# LedBtn.net
KiCad netlist of a schematic drawn in Altium Designer
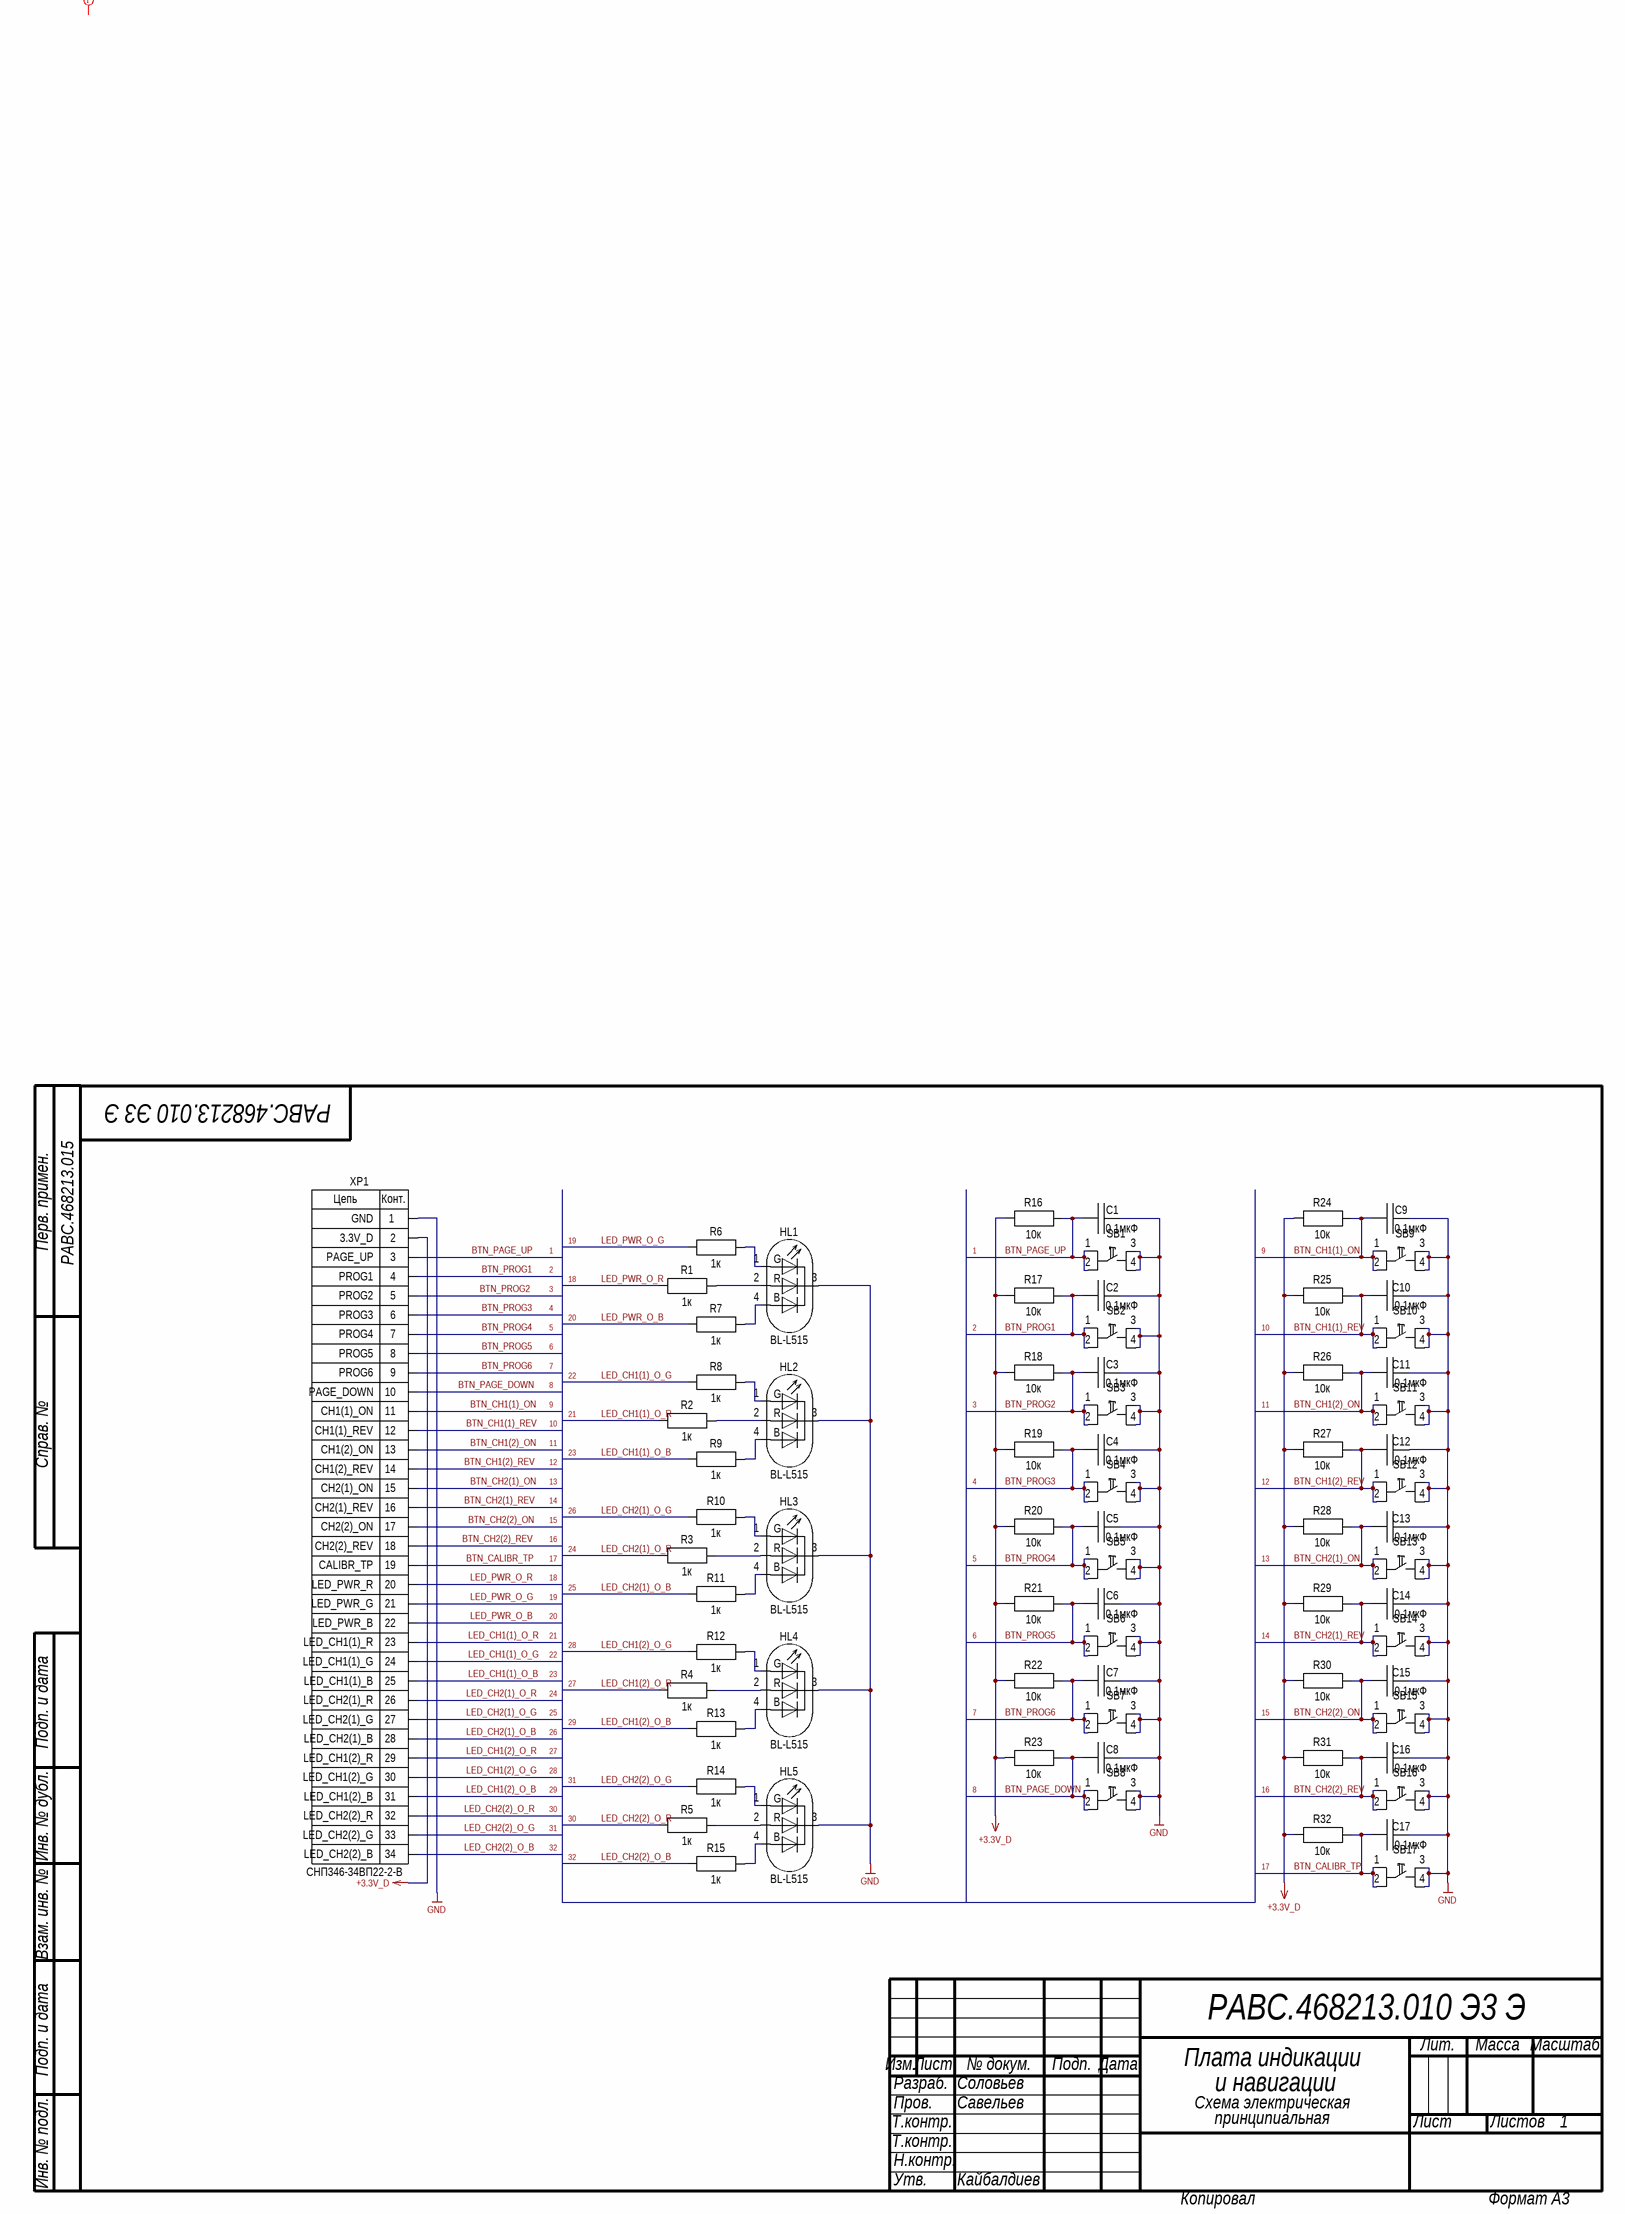
[diagram p0: LedBtn.SchDoc]

(export (version "E")
  (design (tool "Eeschema 10.0.6"))
  (components
    (comp (ref "C1")
      (value "0,1мкФ")
      (footprint "Cap0805")
      (fields
        (field (name "PARTNUMBER") "К10-84в-2012М-50 В-Н90-0,1 мкФ+80 %-20 %-N-A")
        (field (name "MANUFACTURER") "ОАО «ВЗРД Монолит»")
        (field (name "Comment") "Capacitor")
      )
      (libsource (lib "AltiumBase new") (part "Capacitor"))
    )
    (comp (ref "C2")
      (value "0,1мкФ")
      (footprint "Cap0805")
      (fields
        (field (name "PARTNUMBER") "К10-84в-2012М-50 В-Н90-0,1 мкФ+80 %-20 %-N-A")
        (field (name "MANUFACTURER") "ОАО «ВЗРД Монолит»")
        (field (name "Comment") "Capacitor")
      )
      (libsource (lib "AltiumBase new") (part "Capacitor"))
    )
    (comp (ref "C3")
      (value "0,1мкФ")
      (footprint "Cap0805")
      (fields
        (field (name "PARTNUMBER") "К10-84в-2012М-50 В-Н90-0,1 мкФ+80 %-20 %-N-A")
        (field (name "MANUFACTURER") "ОАО «ВЗРД Монолит»")
        (field (name "Comment") "Capacitor")
      )
      (libsource (lib "AltiumBase new") (part "Capacitor"))
    )
    (comp (ref "C4")
      (value "0,1мкФ")
      (footprint "Cap0805")
      (fields
        (field (name "PARTNUMBER") "К10-84в-2012М-50 В-Н90-0,1 мкФ+80 %-20 %-N-A")
        (field (name "MANUFACTURER") "ОАО «ВЗРД Монолит»")
        (field (name "Comment") "Capacitor")
      )
      (libsource (lib "AltiumBase new") (part "Capacitor"))
    )
    (comp (ref "C5")
      (value "0,1мкФ")
      (footprint "Cap0805")
      (fields
        (field (name "PARTNUMBER") "К10-84в-2012М-50 В-Н90-0,1 мкФ+80 %-20 %-N-A")
        (field (name "MANUFACTURER") "ОАО «ВЗРД Монолит»")
        (field (name "Comment") "Capacitor")
      )
      (libsource (lib "AltiumBase new") (part "Capacitor"))
    )
    (comp (ref "C6")
      (value "0,1мкФ")
      (footprint "Cap0805")
      (fields
        (field (name "PARTNUMBER") "К10-84в-2012М-50 В-Н90-0,1 мкФ+80 %-20 %-N-A")
        (field (name "MANUFACTURER") "ОАО «ВЗРД Монолит»")
        (field (name "Comment") "Capacitor")
      )
      (libsource (lib "AltiumBase new") (part "Capacitor"))
    )
    (comp (ref "C7")
      (value "0,1мкФ")
      (footprint "Cap0805")
      (fields
        (field (name "PARTNUMBER") "К10-84в-2012М-50 В-Н90-0,1 мкФ+80 %-20 %-N-A")
        (field (name "MANUFACTURER") "ОАО «ВЗРД Монолит»")
        (field (name "Comment") "Capacitor")
      )
      (libsource (lib "AltiumBase new") (part "Capacitor"))
    )
    (comp (ref "C8")
      (value "0,1мкФ")
      (footprint "Cap0805")
      (fields
        (field (name "PARTNUMBER") "К10-84в-2012М-50 В-Н90-0,1 мкФ+80 %-20 %-N-A")
        (field (name "MANUFACTURER") "ОАО «ВЗРД Монолит»")
        (field (name "Comment") "Capacitor")
      )
      (libsource (lib "AltiumBase new") (part "Capacitor"))
    )
    (comp (ref "C9")
      (value "0,1мкФ")
      (footprint "Cap0805")
      (fields
        (field (name "PARTNUMBER") "К10-84в-2012М-50 В-Н90-0,1 мкФ+80 %-20 %-N-A")
        (field (name "MANUFACTURER") "ОАО «ВЗРД Монолит»")
        (field (name "Comment") "Capacitor")
      )
      (libsource (lib "AltiumBase new") (part "Capacitor"))
    )
    (comp (ref "C10")
      (value "0,1мкФ")
      (footprint "Cap0805")
      (fields
        (field (name "PARTNUMBER") "К10-84в-2012М-50 В-Н90-0,1 мкФ+80 %-20 %-N-A")
        (field (name "MANUFACTURER") "ОАО «ВЗРД Монолит»")
        (field (name "Comment") "Capacitor")
      )
      (libsource (lib "AltiumBase new") (part "Capacitor"))
    )
    (comp (ref "C11")
      (value "0,1мкФ")
      (footprint "Cap0805")
      (fields
        (field (name "PARTNUMBER") "К10-84в-2012М-50 В-Н90-0,1 мкФ+80 %-20 %-N-A")
        (field (name "MANUFACTURER") "ОАО «ВЗРД Монолит»")
        (field (name "Comment") "Capacitor")
      )
      (libsource (lib "AltiumBase new") (part "Capacitor"))
    )
    (comp (ref "C12")
      (value "0,1мкФ")
      (footprint "Cap0805")
      (fields
        (field (name "PARTNUMBER") "К10-84в-2012М-50 В-Н90-0,1 мкФ+80 %-20 %-N-A")
        (field (name "MANUFACTURER") "ОАО «ВЗРД Монолит»")
        (field (name "Comment") "Capacitor")
      )
      (libsource (lib "AltiumBase new") (part "Capacitor"))
    )
    (comp (ref "C13")
      (value "0,1мкФ")
      (footprint "Cap0805")
      (fields
        (field (name "PARTNUMBER") "К10-84в-2012М-50 В-Н90-0,1 мкФ+80 %-20 %-N-A")
        (field (name "MANUFACTURER") "ОАО «ВЗРД Монолит»")
        (field (name "Comment") "Capacitor")
      )
      (libsource (lib "AltiumBase new") (part "Capacitor"))
    )
    (comp (ref "C14")
      (value "0,1мкФ")
      (footprint "Cap0805")
      (fields
        (field (name "PARTNUMBER") "К10-84в-2012М-50 В-Н90-0,1 мкФ+80 %-20 %-N-A")
        (field (name "MANUFACTURER") "ОАО «ВЗРД Монолит»")
        (field (name "Comment") "Capacitor")
      )
      (libsource (lib "AltiumBase new") (part "Capacitor"))
    )
    (comp (ref "C15")
      (value "0,1мкФ")
      (footprint "Cap0805")
      (fields
        (field (name "PARTNUMBER") "К10-84в-2012М-50 В-Н90-0,1 мкФ+80 %-20 %-N-A")
        (field (name "MANUFACTURER") "ОАО «ВЗРД Монолит»")
        (field (name "Comment") "Capacitor")
      )
      (libsource (lib "AltiumBase new") (part "Capacitor"))
    )
    (comp (ref "C16")
      (value "0,1мкФ")
      (footprint "Cap0805")
      (fields
        (field (name "PARTNUMBER") "К10-84в-2012М-50 В-Н90-0,1 мкФ+80 %-20 %-N-A")
        (field (name "MANUFACTURER") "ОАО «ВЗРД Монолит»")
        (field (name "Comment") "Capacitor")
      )
      (libsource (lib "AltiumBase new") (part "Capacitor"))
    )
    (comp (ref "C17")
      (value "0,1мкФ")
      (footprint "Cap0805")
      (fields
        (field (name "PARTNUMBER") "К10-84в-2012М-50 В-Н90-0,1 мкФ+80 %-20 %-N-A")
        (field (name "MANUFACTURER") "ОАО «ВЗРД Монолит»")
        (field (name "Comment") "Capacitor")
      )
      (libsource (lib "AltiumBase new") (part "Capacitor"))
    )
    (comp (ref "HL1")
      (value "LED-RGB_C")
      (footprint "BL-L515")
      (description "Светодиод RGB с общим анодом BL-L515RGBW-CA")
      (fields
        (field (name "NAME") "BL-L515")
        (field (name "MANUFACTURER") "Betlux Electronics")
        (field (name "PARTNUMBER") "Светодиод BL-L515RGBW-CС")
      )
      (libsource (lib "AltiumBase new") (part "LED-RGB_C"))
    )
    (comp (ref "HL2")
      (value "LED-RGB_C")
      (footprint "BL-L515")
      (description "Светодиод RGB с общим анодом BL-L515RGBW-CA")
      (fields
        (field (name "NAME") "BL-L515")
        (field (name "MANUFACTURER") "Betlux Electronics")
        (field (name "PARTNUMBER") "Светодиод BL-L515RGBW-CС")
      )
      (libsource (lib "AltiumBase new") (part "LED-RGB_C"))
    )
    (comp (ref "HL3")
      (value "LED-RGB_C")
      (footprint "BL-L515")
      (description "Светодиод RGB с общим анодом BL-L515RGBW-CA")
      (fields
        (field (name "NAME") "BL-L515")
        (field (name "MANUFACTURER") "Betlux Electronics")
        (field (name "PARTNUMBER") "Светодиод BL-L515RGBW-CС")
      )
      (libsource (lib "AltiumBase new") (part "LED-RGB_C"))
    )
    (comp (ref "HL4")
      (value "LED-RGB_C")
      (footprint "BL-L515")
      (description "Светодиод RGB с общим анодом BL-L515RGBW-CA")
      (fields
        (field (name "NAME") "BL-L515")
        (field (name "MANUFACTURER") "Betlux Electronics")
        (field (name "PARTNUMBER") "Светодиод BL-L515RGBW-CС")
      )
      (libsource (lib "AltiumBase new") (part "LED-RGB_C"))
    )
    (comp (ref "HL5")
      (value "LED-RGB_C")
      (footprint "BL-L515")
      (description "Светодиод RGB с общим анодом BL-L515RGBW-CA")
      (fields
        (field (name "NAME") "BL-L515")
        (field (name "MANUFACTURER") "Betlux Electronics")
        (field (name "PARTNUMBER") "Светодиод BL-L515RGBW-CС")
      )
      (libsource (lib "AltiumBase new") (part "LED-RGB_C"))
    )
    (comp (ref "R1")
      (value "1к")
      (footprint "Res0805")
      (fields
        (field (name "MANUFACTURER") "АО «НПО «Эркон»")
        (field (name "PARTNUMBER") "Р1-8В-0,125-1 кОм±5 %-Т-А")
        (field (name "Comment") "Resistor0125")
      )
      (libsource (lib "AltiumBase new") (part "Resistor0125"))
    )
    (comp (ref "R2")
      (value "1к")
      (footprint "Res0805")
      (fields
        (field (name "MANUFACTURER") "АО «НПО «Эркон»")
        (field (name "PARTNUMBER") "Р1-8В-0,125-1 кОм±5 %-Т-А")
        (field (name "Comment") "Resistor0125")
      )
      (libsource (lib "AltiumBase new") (part "Resistor0125"))
    )
    (comp (ref "R3")
      (value "1к")
      (footprint "Res0805")
      (fields
        (field (name "MANUFACTURER") "АО «НПО «Эркон»")
        (field (name "PARTNUMBER") "Р1-8В-0,125-1 кОм±5 %-Т-А")
        (field (name "Comment") "Resistor0125")
      )
      (libsource (lib "AltiumBase new") (part "Resistor0125"))
    )
    (comp (ref "R4")
      (value "1к")
      (footprint "Res0805")
      (fields
        (field (name "MANUFACTURER") "АО «НПО «Эркон»")
        (field (name "PARTNUMBER") "Р1-8В-0,125-1 кОм±5 %-Т-А")
        (field (name "Comment") "Resistor0125")
      )
      (libsource (lib "AltiumBase new") (part "Resistor0125"))
    )
    (comp (ref "R5")
      (value "1к")
      (footprint "Res0805")
      (fields
        (field (name "MANUFACTURER") "АО «НПО «Эркон»")
        (field (name "PARTNUMBER") "Р1-8В-0,125-1 кОм±5 %-Т-А")
        (field (name "Comment") "Resistor0125")
      )
      (libsource (lib "AltiumBase new") (part "Resistor0125"))
    )
    (comp (ref "R6")
      (value "1к")
      (footprint "Res0805")
      (fields
        (field (name "MANUFACTURER") "АО «НПО «Эркон»")
        (field (name "PARTNUMBER") "Р1-8В-0,125-1 кОм±5 %-Т-А")
        (field (name "Comment") "Resistor0125")
      )
      (libsource (lib "AltiumBase new") (part "Resistor0125"))
    )
    (comp (ref "R7")
      (value "1к")
      (footprint "Res0805")
      (fields
        (field (name "MANUFACTURER") "АО «НПО «Эркон»")
        (field (name "PARTNUMBER") "Р1-8В-0,125-1 кОм±5 %-Т-А")
        (field (name "Comment") "Resistor0125")
      )
      (libsource (lib "AltiumBase new") (part "Resistor0125"))
    )
    (comp (ref "R8")
      (value "1к")
      (footprint "Res0805")
      (fields
        (field (name "MANUFACTURER") "АО «НПО «Эркон»")
        (field (name "PARTNUMBER") "Р1-8В-0,125-1 кОм±5 %-Т-А")
        (field (name "Comment") "Resistor0125")
      )
      (libsource (lib "AltiumBase new") (part "Resistor0125"))
    )
    (comp (ref "R9")
      (value "1к")
      (footprint "Res0805")
      (fields
        (field (name "MANUFACTURER") "АО «НПО «Эркон»")
        (field (name "PARTNUMBER") "Р1-8В-0,125-1 кОм±5 %-Т-А")
        (field (name "Comment") "Resistor0125")
      )
      (libsource (lib "AltiumBase new") (part "Resistor0125"))
    )
    (comp (ref "R10")
      (value "1к")
      (footprint "Res0805")
      (fields
        (field (name "MANUFACTURER") "АО «НПО «Эркон»")
        (field (name "PARTNUMBER") "Р1-8В-0,125-1 кОм±5 %-Т-А")
        (field (name "Comment") "Resistor0125")
      )
      (libsource (lib "AltiumBase new") (part "Resistor0125"))
    )
    (comp (ref "R11")
      (value "1к")
      (footprint "Res0805")
      (fields
        (field (name "MANUFACTURER") "АО «НПО «Эркон»")
        (field (name "PARTNUMBER") "Р1-8В-0,125-1 кОм±5 %-Т-А")
        (field (name "Comment") "Resistor0125")
      )
      (libsource (lib "AltiumBase new") (part "Resistor0125"))
    )
    (comp (ref "R12")
      (value "1к")
      (footprint "Res0805")
      (fields
        (field (name "MANUFACTURER") "АО «НПО «Эркон»")
        (field (name "PARTNUMBER") "Р1-8В-0,125-1 кОм±5 %-Т-А")
        (field (name "Comment") "Resistor0125")
      )
      (libsource (lib "AltiumBase new") (part "Resistor0125"))
    )
    (comp (ref "R13")
      (value "1к")
      (footprint "Res0805")
      (fields
        (field (name "MANUFACTURER") "АО «НПО «Эркон»")
        (field (name "PARTNUMBER") "Р1-8В-0,125-1 кОм±5 %-Т-А")
        (field (name "Comment") "Resistor0125")
      )
      (libsource (lib "AltiumBase new") (part "Resistor0125"))
    )
    (comp (ref "R14")
      (value "1к")
      (footprint "Res0805")
      (fields
        (field (name "MANUFACTURER") "АО «НПО «Эркон»")
        (field (name "PARTNUMBER") "Р1-8В-0,125-1 кОм±5 %-Т-А")
        (field (name "Comment") "Resistor0125")
      )
      (libsource (lib "AltiumBase new") (part "Resistor0125"))
    )
    (comp (ref "R15")
      (value "1к")
      (footprint "Res0805")
      (fields
        (field (name "MANUFACTURER") "АО «НПО «Эркон»")
        (field (name "PARTNUMBER") "Р1-8В-0,125-1 кОм±5 %-Т-А")
        (field (name "Comment") "Resistor0125")
      )
      (libsource (lib "AltiumBase new") (part "Resistor0125"))
    )
    (comp (ref "R16")
      (value "10к")
      (footprint "Res0603")
      (fields
        (field (name "MANUFACTURER") "АО «НПО «Эркон»")
        (field (name "PARTNUMBER") "Р1-8В-0,1-10 кОм±5 %-Т-А")
        (field (name "Comment") "Resistor01")
      )
      (libsource (lib "AltiumBase new") (part "Resistor01"))
    )
    (comp (ref "R17")
      (value "10к")
      (footprint "Res0603")
      (fields
        (field (name "MANUFACTURER") "АО «НПО «Эркон»")
        (field (name "PARTNUMBER") "Р1-8В-0,1-10 кОм±5 %-Т-А")
        (field (name "Comment") "Resistor01")
      )
      (libsource (lib "AltiumBase new") (part "Resistor01"))
    )
    (comp (ref "R18")
      (value "10к")
      (footprint "Res0603")
      (fields
        (field (name "MANUFACTURER") "АО «НПО «Эркон»")
        (field (name "PARTNUMBER") "Р1-8В-0,1-10 кОм±5 %-Т-А")
        (field (name "Comment") "Resistor01")
      )
      (libsource (lib "AltiumBase new") (part "Resistor01"))
    )
    (comp (ref "R19")
      (value "10к")
      (footprint "Res0603")
      (fields
        (field (name "MANUFACTURER") "АО «НПО «Эркон»")
        (field (name "PARTNUMBER") "Р1-8В-0,1-10 кОм±5 %-Т-А")
        (field (name "Comment") "Resistor01")
      )
      (libsource (lib "AltiumBase new") (part "Resistor01"))
    )
    (comp (ref "R20")
      (value "10к")
      (footprint "Res0603")
      (fields
        (field (name "MANUFACTURER") "АО «НПО «Эркон»")
        (field (name "PARTNUMBER") "Р1-8В-0,1-10 кОм±5 %-Т-А")
        (field (name "Comment") "Resistor01")
      )
      (libsource (lib "AltiumBase new") (part "Resistor01"))
    )
    (comp (ref "R21")
      (value "10к")
      (footprint "Res0603")
      (fields
        (field (name "MANUFACTURER") "АО «НПО «Эркон»")
        (field (name "PARTNUMBER") "Р1-8В-0,1-10 кОм±5 %-Т-А")
        (field (name "Comment") "Resistor01")
      )
      (libsource (lib "AltiumBase new") (part "Resistor01"))
    )
    (comp (ref "R22")
      (value "10к")
      (footprint "Res0603")
      (fields
        (field (name "MANUFACTURER") "АО «НПО «Эркон»")
        (field (name "PARTNUMBER") "Р1-8В-0,1-10 кОм±5 %-Т-А")
        (field (name "Comment") "Resistor01")
      )
      (libsource (lib "AltiumBase new") (part "Resistor01"))
    )
    (comp (ref "R23")
      (value "10к")
      (footprint "Res0603")
      (fields
        (field (name "MANUFACTURER") "АО «НПО «Эркон»")
        (field (name "PARTNUMBER") "Р1-8В-0,1-10 кОм±5 %-Т-А")
        (field (name "Comment") "Resistor01")
      )
      (libsource (lib "AltiumBase new") (part "Resistor01"))
    )
    (comp (ref "R24")
      (value "10к")
      (footprint "Res0603")
      (fields
        (field (name "MANUFACTURER") "АО «НПО «Эркон»")
        (field (name "PARTNUMBER") "Р1-8В-0,1-10 кОм±5 %-Т-А")
        (field (name "Comment") "Resistor01")
      )
      (libsource (lib "AltiumBase new") (part "Resistor01"))
    )
    (comp (ref "R25")
      (value "10к")
      (footprint "Res0603")
      (fields
        (field (name "MANUFACTURER") "АО «НПО «Эркон»")
        (field (name "PARTNUMBER") "Р1-8В-0,1-10 кОм±5 %-Т-А")
        (field (name "Comment") "Resistor01")
      )
      (libsource (lib "AltiumBase new") (part "Resistor01"))
    )
    (comp (ref "R26")
      (value "10к")
      (footprint "Res0603")
      (fields
        (field (name "MANUFACTURER") "АО «НПО «Эркон»")
        (field (name "PARTNUMBER") "Р1-8В-0,1-10 кОм±5 %-Т-А")
        (field (name "Comment") "Resistor01")
      )
      (libsource (lib "AltiumBase new") (part "Resistor01"))
    )
    (comp (ref "R27")
      (value "10к")
      (footprint "Res0603")
      (fields
        (field (name "MANUFACTURER") "АО «НПО «Эркон»")
        (field (name "PARTNUMBER") "Р1-8В-0,1-10 кОм±5 %-Т-А")
        (field (name "Comment") "Resistor01")
      )
      (libsource (lib "AltiumBase new") (part "Resistor01"))
    )
    (comp (ref "R28")
      (value "10к")
      (footprint "Res0603")
      (fields
        (field (name "MANUFACTURER") "АО «НПО «Эркон»")
        (field (name "PARTNUMBER") "Р1-8В-0,1-10 кОм±5 %-Т-А")
        (field (name "Comment") "Resistor01")
      )
      (libsource (lib "AltiumBase new") (part "Resistor01"))
    )
    (comp (ref "R29")
      (value "10к")
      (footprint "Res0603")
      (fields
        (field (name "MANUFACTURER") "АО «НПО «Эркон»")
        (field (name "PARTNUMBER") "Р1-8В-0,1-10 кОм±5 %-Т-А")
        (field (name "Comment") "Resistor01")
      )
      (libsource (lib "AltiumBase new") (part "Resistor01"))
    )
    (comp (ref "R30")
      (value "10к")
      (footprint "Res0603")
      (fields
        (field (name "MANUFACTURER") "АО «НПО «Эркон»")
        (field (name "PARTNUMBER") "Р1-8В-0,1-10 кОм±5 %-Т-А")
        (field (name "Comment") "Resistor01")
      )
      (libsource (lib "AltiumBase new") (part "Resistor01"))
    )
    (comp (ref "R31")
      (value "10к")
      (footprint "Res0603")
      (fields
        (field (name "MANUFACTURER") "АО «НПО «Эркон»")
        (field (name "PARTNUMBER") "Р1-8В-0,1-10 кОм±5 %-Т-А")
        (field (name "Comment") "Resistor01")
      )
      (libsource (lib "AltiumBase new") (part "Resistor01"))
    )
    (comp (ref "R32")
      (value "10к")
      (footprint "Res0603")
      (fields
        (field (name "MANUFACTURER") "АО «НПО «Эркон»")
        (field (name "PARTNUMBER") "Р1-8В-0,1-10 кОм±5 %-Т-А")
        (field (name "Comment") "Resistor01")
      )
      (libsource (lib "AltiumBase new") (part "Resistor01"))
    )
    (comp (ref "SB1")
      (value "Knopka")
      (footprint "Switch_tact_11mm")
      (fields
        (field (name "MANUFACTURER") "KLS Electronic")
        (field (name "PARTNUMBER") "Кнопка тактовая прямая KLS7-TS6601-11-180")
      )
      (libsource (lib "AltiumBase new") (part "Knopka"))
    )
    (comp (ref "SB2")
      (value "Knopka")
      (footprint "Switch_tact_11mm")
      (fields
        (field (name "MANUFACTURER") "KLS Electronic")
        (field (name "PARTNUMBER") "Кнопка тактовая прямая KLS7-TS6601-11-180")
      )
      (libsource (lib "AltiumBase new") (part "Knopka"))
    )
    (comp (ref "SB3")
      (value "Knopka")
      (footprint "Switch_tact_11mm")
      (fields
        (field (name "MANUFACTURER") "KLS Electronic")
        (field (name "PARTNUMBER") "Кнопка тактовая прямая KLS7-TS6601-11-180")
      )
      (libsource (lib "AltiumBase new") (part "Knopka"))
    )
    (comp (ref "SB4")
      (value "Knopka")
      (footprint "Switch_tact_11mm")
      (fields
        (field (name "MANUFACTURER") "KLS Electronic")
        (field (name "PARTNUMBER") "Кнопка тактовая прямая KLS7-TS6601-11-180")
      )
      (libsource (lib "AltiumBase new") (part "Knopka"))
    )
    (comp (ref "SB5")
      (value "Knopka")
      (footprint "Switch_tact_11mm")
      (fields
        (field (name "MANUFACTURER") "KLS Electronic")
        (field (name "PARTNUMBER") "Кнопка тактовая прямая KLS7-TS6601-11-180")
      )
      (libsource (lib "AltiumBase new") (part "Knopka"))
    )
    (comp (ref "SB6")
      (value "Knopka")
      (footprint "Switch_tact_11mm")
      (fields
        (field (name "MANUFACTURER") "KLS Electronic")
        (field (name "PARTNUMBER") "Кнопка тактовая прямая KLS7-TS6601-11-180")
      )
      (libsource (lib "AltiumBase new") (part "Knopka"))
    )
    (comp (ref "SB7")
      (value "Knopka")
      (footprint "Switch_tact_11mm")
      (fields
        (field (name "MANUFACTURER") "KLS Electronic")
        (field (name "PARTNUMBER") "Кнопка тактовая прямая KLS7-TS6601-11-180")
      )
      (libsource (lib "AltiumBase new") (part "Knopka"))
    )
    (comp (ref "SB8")
      (value "Knopka")
      (footprint "Switch_tact_11mm")
      (fields
        (field (name "MANUFACTURER") "KLS Electronic")
        (field (name "PARTNUMBER") "Кнопка тактовая прямая KLS7-TS6601-11-180")
      )
      (libsource (lib "AltiumBase new") (part "Knopka"))
    )
    (comp (ref "SB9")
      (value "Knopka")
      (footprint "Switch_tact_11mm")
      (fields
        (field (name "MANUFACTURER") "KLS Electronic")
        (field (name "PARTNUMBER") "Кнопка тактовая прямая KLS7-TS6601-11-180")
      )
      (libsource (lib "AltiumBase new") (part "Knopka"))
    )
    (comp (ref "SB10")
      (value "Knopka")
      (footprint "Switch_tact_11mm")
      (fields
        (field (name "MANUFACTURER") "KLS Electronic")
        (field (name "PARTNUMBER") "Кнопка тактовая прямая KLS7-TS6601-11-180")
      )
      (libsource (lib "AltiumBase new") (part "Knopka"))
    )
    (comp (ref "SB11")
      (value "Knopka")
      (footprint "Switch_tact_11mm")
      (fields
        (field (name "MANUFACTURER") "KLS Electronic")
        (field (name "PARTNUMBER") "Кнопка тактовая прямая KLS7-TS6601-11-180")
      )
      (libsource (lib "AltiumBase new") (part "Knopka"))
    )
    (comp (ref "SB12")
      (value "Knopka")
      (footprint "Switch_tact_11mm")
      (fields
        (field (name "MANUFACTURER") "KLS Electronic")
        (field (name "PARTNUMBER") "Кнопка тактовая прямая KLS7-TS6601-11-180")
      )
      (libsource (lib "AltiumBase new") (part "Knopka"))
    )
    (comp (ref "SB13")
      (value "Knopka")
      (footprint "Switch_tact_11mm")
      (fields
        (field (name "MANUFACTURER") "KLS Electronic")
        (field (name "PARTNUMBER") "Кнопка тактовая прямая KLS7-TS6601-11-180")
      )
      (libsource (lib "AltiumBase new") (part "Knopka"))
    )
    (comp (ref "SB14")
      (value "Knopka")
      (footprint "Switch_tact_11mm")
      (fields
        (field (name "MANUFACTURER") "KLS Electronic")
        (field (name "PARTNUMBER") "Кнопка тактовая прямая KLS7-TS6601-11-180")
      )
      (libsource (lib "AltiumBase new") (part "Knopka"))
    )
    (comp (ref "SB15")
      (value "Knopka")
      (footprint "Switch_tact_11mm")
      (fields
        (field (name "MANUFACTURER") "KLS Electronic")
        (field (name "PARTNUMBER") "Кнопка тактовая прямая KLS7-TS6601-11-180")
      )
      (libsource (lib "AltiumBase new") (part "Knopka"))
    )
    (comp (ref "SB16")
      (value "Knopka")
      (footprint "Switch_tact_11mm")
      (fields
        (field (name "MANUFACTURER") "KLS Electronic")
        (field (name "PARTNUMBER") "Кнопка тактовая прямая KLS7-TS6601-11-180")
      )
      (libsource (lib "AltiumBase new") (part "Knopka"))
    )
    (comp (ref "SB17")
      (value "Knopka")
      (footprint "Switch_tact_11mm")
      (fields
        (field (name "MANUFACTURER") "KLS Electronic")
        (field (name "PARTNUMBER") "Кнопка тактовая прямая KLS7-TS6601-11-180")
      )
      (libsource (lib "AltiumBase new") (part "Knopka"))
    )
    (comp (ref "XP1")
      (value "ConnectorP34")
      (footprint "PLD-34")
      (fields
        (field (name "MANUFACTURER") "АО «Карачевский завод Электродеталь»")
        (field (name "PARTNUMBER") "Вилка СНП346-34ВП22-2-В")
      )
      (libsource (lib "AltiumBase new") (part "ConnectorP34"))
    )
  )
  (nets
    (net (code "1") (name "+3.3V_D") (class "Default")
      (node (ref "R16") (pin "2") (pinfunction "2_2") (pintype "passive"))
      (node (ref "R17") (pin "2") (pinfunction "2_2") (pintype "passive"))
      (node (ref "R18") (pin "2") (pinfunction "2_2") (pintype "passive"))
      (node (ref "R19") (pin "2") (pinfunction "2_2") (pintype "passive"))
      (node (ref "R20") (pin "2") (pinfunction "2_2") (pintype "passive"))
      (node (ref "R21") (pin "2") (pinfunction "2_2") (pintype "passive"))
      (node (ref "R22") (pin "2") (pinfunction "2_2") (pintype "passive"))
      (node (ref "R23") (pin "2") (pinfunction "2_2") (pintype "passive"))
      (node (ref "R24") (pin "2") (pinfunction "2_2") (pintype "passive"))
      (node (ref "R25") (pin "2") (pinfunction "2_2") (pintype "passive"))
      (node (ref "R26") (pin "2") (pinfunction "2_2") (pintype "passive"))
      (node (ref "R27") (pin "2") (pinfunction "2_2") (pintype "passive"))
      (node (ref "R28") (pin "2") (pinfunction "2_2") (pintype "passive"))
      (node (ref "R29") (pin "2") (pinfunction "2_2") (pintype "passive"))
      (node (ref "R30") (pin "2") (pinfunction "2_2") (pintype "passive"))
      (node (ref "R31") (pin "2") (pinfunction "2_2") (pintype "passive"))
      (node (ref "R32") (pin "2") (pinfunction "2_2") (pintype "passive"))
      (node (ref "XP1") (pin "2") (pinfunction "2_2") (pintype "passive"))
    )
    (net (code "2") (name "/BTN_CALIBR_TP") (class "Default")
      (node (ref "C17") (pin "2") (pinfunction "2_2") (pintype "passive"))
      (node (ref "R32") (pin "1") (pinfunction "1_1") (pintype "passive"))
      (node (ref "SB17") (pin "1") (pinfunction "1_1") (pintype "passive"))
      (node (ref "SB17") (pin "2") (pinfunction "2_2") (pintype "passive"))
      (node (ref "XP1") (pin "19") (pinfunction "19_19") (pintype "passive"))
    )
    (net (code "3") (name "/BTN_CH1(1)_ON") (class "Default")
      (node (ref "C9") (pin "2") (pinfunction "2_2") (pintype "passive"))
      (node (ref "R24") (pin "1") (pinfunction "1_1") (pintype "passive"))
      (node (ref "SB9") (pin "1") (pinfunction "1_1") (pintype "passive"))
      (node (ref "SB9") (pin "2") (pinfunction "2_2") (pintype "passive"))
      (node (ref "XP1") (pin "11") (pinfunction "11_11") (pintype "passive"))
    )
    (net (code "4") (name "/BTN_CH1(1)_REV") (class "Default")
      (node (ref "C10") (pin "2") (pinfunction "2_2") (pintype "passive"))
      (node (ref "R25") (pin "1") (pinfunction "1_1") (pintype "passive"))
      (node (ref "SB10") (pin "1") (pinfunction "1_1") (pintype "passive"))
      (node (ref "SB10") (pin "2") (pinfunction "2_2") (pintype "passive"))
      (node (ref "XP1") (pin "12") (pinfunction "12_12") (pintype "passive"))
    )
    (net (code "5") (name "/BTN_CH1(2)_ON") (class "Default")
      (node (ref "C11") (pin "2") (pinfunction "2_2") (pintype "passive"))
      (node (ref "R26") (pin "1") (pinfunction "1_1") (pintype "passive"))
      (node (ref "SB11") (pin "1") (pinfunction "1_1") (pintype "passive"))
      (node (ref "SB11") (pin "2") (pinfunction "2_2") (pintype "passive"))
      (node (ref "XP1") (pin "13") (pinfunction "13_13") (pintype "passive"))
    )
    (net (code "6") (name "/BTN_CH1(2)_REV") (class "Default")
      (node (ref "C12") (pin "2") (pinfunction "2_2") (pintype "passive"))
      (node (ref "R27") (pin "1") (pinfunction "1_1") (pintype "passive"))
      (node (ref "SB12") (pin "1") (pinfunction "1_1") (pintype "passive"))
      (node (ref "SB12") (pin "2") (pinfunction "2_2") (pintype "passive"))
      (node (ref "XP1") (pin "14") (pinfunction "14_14") (pintype "passive"))
    )
    (net (code "7") (name "/BTN_CH2(1)_ON") (class "Default")
      (node (ref "C13") (pin "2") (pinfunction "2_2") (pintype "passive"))
      (node (ref "R28") (pin "1") (pinfunction "1_1") (pintype "passive"))
      (node (ref "SB13") (pin "1") (pinfunction "1_1") (pintype "passive"))
      (node (ref "SB13") (pin "2") (pinfunction "2_2") (pintype "passive"))
      (node (ref "XP1") (pin "15") (pinfunction "15_15") (pintype "passive"))
    )
    (net (code "8") (name "/BTN_CH2(1)_REV") (class "Default")
      (node (ref "C14") (pin "2") (pinfunction "2_2") (pintype "passive"))
      (node (ref "R29") (pin "1") (pinfunction "1_1") (pintype "passive"))
      (node (ref "SB14") (pin "1") (pinfunction "1_1") (pintype "passive"))
      (node (ref "SB14") (pin "2") (pinfunction "2_2") (pintype "passive"))
      (node (ref "XP1") (pin "16") (pinfunction "16_16") (pintype "passive"))
    )
    (net (code "9") (name "/BTN_CH2(2)_ON") (class "Default")
      (node (ref "C15") (pin "2") (pinfunction "2_2") (pintype "passive"))
      (node (ref "R30") (pin "1") (pinfunction "1_1") (pintype "passive"))
      (node (ref "SB15") (pin "1") (pinfunction "1_1") (pintype "passive"))
      (node (ref "SB15") (pin "2") (pinfunction "2_2") (pintype "passive"))
      (node (ref "XP1") (pin "17") (pinfunction "17_17") (pintype "passive"))
    )
    (net (code "10") (name "/BTN_CH2(2)_REV") (class "Default")
      (node (ref "C16") (pin "2") (pinfunction "2_2") (pintype "passive"))
      (node (ref "R31") (pin "1") (pinfunction "1_1") (pintype "passive"))
      (node (ref "SB16") (pin "1") (pinfunction "1_1") (pintype "passive"))
      (node (ref "SB16") (pin "2") (pinfunction "2_2") (pintype "passive"))
      (node (ref "XP1") (pin "18") (pinfunction "18_18") (pintype "passive"))
    )
    (net (code "11") (name "/BTN_PAGE_DOWN") (class "Default")
      (node (ref "C8") (pin "2") (pinfunction "2_2") (pintype "passive"))
      (node (ref "R23") (pin "1") (pinfunction "1_1") (pintype "passive"))
      (node (ref "SB8") (pin "1") (pinfunction "1_1") (pintype "passive"))
      (node (ref "SB8") (pin "2") (pinfunction "2_2") (pintype "passive"))
      (node (ref "XP1") (pin "10") (pinfunction "10_10") (pintype "passive"))
    )
    (net (code "12") (name "/BTN_PAGE_UP") (class "Default")
      (node (ref "C1") (pin "2") (pinfunction "2_2") (pintype "passive"))
      (node (ref "R16") (pin "1") (pinfunction "1_1") (pintype "passive"))
      (node (ref "SB1") (pin "1") (pinfunction "1_1") (pintype "passive"))
      (node (ref "SB1") (pin "2") (pinfunction "2_2") (pintype "passive"))
      (node (ref "XP1") (pin "3") (pinfunction "3_3") (pintype "passive"))
    )
    (net (code "13") (name "/BTN_PROG1") (class "Default")
      (node (ref "C2") (pin "2") (pinfunction "2_2") (pintype "passive"))
      (node (ref "R17") (pin "1") (pinfunction "1_1") (pintype "passive"))
      (node (ref "SB2") (pin "1") (pinfunction "1_1") (pintype "passive"))
      (node (ref "SB2") (pin "2") (pinfunction "2_2") (pintype "passive"))
      (node (ref "XP1") (pin "4") (pinfunction "4_4") (pintype "passive"))
    )
    (net (code "14") (name "/BTN_PROG2") (class "Default")
      (node (ref "C3") (pin "2") (pinfunction "2_2") (pintype "passive"))
      (node (ref "R18") (pin "1") (pinfunction "1_1") (pintype "passive"))
      (node (ref "SB3") (pin "1") (pinfunction "1_1") (pintype "passive"))
      (node (ref "SB3") (pin "2") (pinfunction "2_2") (pintype "passive"))
      (node (ref "XP1") (pin "5") (pinfunction "5_5") (pintype "passive"))
    )
    (net (code "15") (name "/BTN_PROG3") (class "Default")
      (node (ref "C4") (pin "2") (pinfunction "2_2") (pintype "passive"))
      (node (ref "R19") (pin "1") (pinfunction "1_1") (pintype "passive"))
      (node (ref "SB4") (pin "1") (pinfunction "1_1") (pintype "passive"))
      (node (ref "SB4") (pin "2") (pinfunction "2_2") (pintype "passive"))
      (node (ref "XP1") (pin "6") (pinfunction "6_6") (pintype "passive"))
    )
    (net (code "16") (name "/BTN_PROG4") (class "Default")
      (node (ref "C5") (pin "2") (pinfunction "2_2") (pintype "passive"))
      (node (ref "R20") (pin "1") (pinfunction "1_1") (pintype "passive"))
      (node (ref "SB5") (pin "1") (pinfunction "1_1") (pintype "passive"))
      (node (ref "SB5") (pin "2") (pinfunction "2_2") (pintype "passive"))
      (node (ref "XP1") (pin "7") (pinfunction "7_7") (pintype "passive"))
    )
    (net (code "17") (name "/BTN_PROG5") (class "Default")
      (node (ref "C6") (pin "2") (pinfunction "2_2") (pintype "passive"))
      (node (ref "R21") (pin "1") (pinfunction "1_1") (pintype "passive"))
      (node (ref "SB6") (pin "1") (pinfunction "1_1") (pintype "passive"))
      (node (ref "SB6") (pin "2") (pinfunction "2_2") (pintype "passive"))
      (node (ref "XP1") (pin "8") (pinfunction "8_8") (pintype "passive"))
    )
    (net (code "18") (name "/BTN_PROG6") (class "Default")
      (node (ref "C7") (pin "2") (pinfunction "2_2") (pintype "passive"))
      (node (ref "R22") (pin "1") (pinfunction "1_1") (pintype "passive"))
      (node (ref "SB7") (pin "1") (pinfunction "1_1") (pintype "passive"))
      (node (ref "SB7") (pin "2") (pinfunction "2_2") (pintype "passive"))
      (node (ref "XP1") (pin "9") (pinfunction "9_9") (pintype "passive"))
    )
    (net (code "19") (name "/LED_CH1(1)_O_B") (class "Default")
      (node (ref "R9") (pin "2") (pinfunction "2_2") (pintype "passive"))
      (node (ref "XP1") (pin "25") (pinfunction "25_25") (pintype "passive"))
    )
    (net (code "20") (name "/LED_CH1(1)_O_G") (class "Default")
      (node (ref "R8") (pin "2") (pinfunction "2_2") (pintype "passive"))
      (node (ref "XP1") (pin "24") (pinfunction "24_24") (pintype "passive"))
    )
    (net (code "21") (name "/LED_CH1(1)_O_R") (class "Default")
      (node (ref "R2") (pin "2") (pinfunction "2_2") (pintype "passive"))
      (node (ref "XP1") (pin "23") (pinfunction "23_23") (pintype "passive"))
    )
    (net (code "22") (name "/LED_CH1(2)_O_B") (class "Default")
      (node (ref "R13") (pin "2") (pinfunction "2_2") (pintype "passive"))
      (node (ref "XP1") (pin "31") (pinfunction "31_31") (pintype "passive"))
    )
    (net (code "23") (name "/LED_CH1(2)_O_G") (class "Default")
      (node (ref "R12") (pin "2") (pinfunction "2_2") (pintype "passive"))
      (node (ref "XP1") (pin "30") (pinfunction "30_30") (pintype "passive"))
    )
    (net (code "24") (name "/LED_CH1(2)_O_R") (class "Default")
      (node (ref "R4") (pin "2") (pinfunction "2_2") (pintype "passive"))
      (node (ref "XP1") (pin "29") (pinfunction "29_29") (pintype "passive"))
    )
    (net (code "25") (name "/LED_CH2(1)_O_B") (class "Default")
      (node (ref "R11") (pin "2") (pinfunction "2_2") (pintype "passive"))
      (node (ref "XP1") (pin "28") (pinfunction "28_28") (pintype "passive"))
    )
    (net (code "26") (name "/LED_CH2(1)_O_G") (class "Default")
      (node (ref "R10") (pin "2") (pinfunction "2_2") (pintype "passive"))
      (node (ref "XP1") (pin "27") (pinfunction "27_27") (pintype "passive"))
    )
    (net (code "27") (name "/LED_CH2(1)_O_R") (class "Default")
      (node (ref "R3") (pin "2") (pinfunction "2_2") (pintype "passive"))
      (node (ref "XP1") (pin "26") (pinfunction "26_26") (pintype "passive"))
    )
    (net (code "28") (name "/LED_CH2(2)_O_B") (class "Default")
      (node (ref "R15") (pin "2") (pinfunction "2_2") (pintype "passive"))
      (node (ref "XP1") (pin "34") (pinfunction "34_34") (pintype "passive"))
    )
    (net (code "29") (name "/LED_CH2(2)_O_G") (class "Default")
      (node (ref "R14") (pin "2") (pinfunction "2_2") (pintype "passive"))
      (node (ref "XP1") (pin "33") (pinfunction "33_33") (pintype "passive"))
    )
    (net (code "30") (name "/LED_CH2(2)_O_R") (class "Default")
      (node (ref "R5") (pin "2") (pinfunction "2_2") (pintype "passive"))
      (node (ref "XP1") (pin "32") (pinfunction "32_32") (pintype "passive"))
    )
    (net (code "31") (name "/LED_PWR_O_B") (class "Default")
      (node (ref "R7") (pin "2") (pinfunction "2_2") (pintype "passive"))
      (node (ref "XP1") (pin "22") (pinfunction "22_22") (pintype "passive"))
    )
    (net (code "32") (name "/LED_PWR_O_G") (class "Default")
      (node (ref "R6") (pin "2") (pinfunction "2_2") (pintype "passive"))
      (node (ref "XP1") (pin "21") (pinfunction "21_21") (pintype "passive"))
    )
    (net (code "33") (name "/LED_PWR_O_R") (class "Default")
      (node (ref "R1") (pin "2") (pinfunction "2_2") (pintype "passive"))
      (node (ref "XP1") (pin "20") (pinfunction "20_20") (pintype "passive"))
    )
    (net (code "34") (name "GND") (class "Default")
      (node (ref "C1") (pin "1") (pinfunction "1_1") (pintype "passive"))
      (node (ref "C10") (pin "1") (pinfunction "1_1") (pintype "passive"))
      (node (ref "C11") (pin "1") (pinfunction "1_1") (pintype "passive"))
      (node (ref "C12") (pin "1") (pinfunction "1_1") (pintype "passive"))
      (node (ref "C13") (pin "1") (pinfunction "1_1") (pintype "passive"))
      (node (ref "C14") (pin "1") (pinfunction "1_1") (pintype "passive"))
      (node (ref "C15") (pin "1") (pinfunction "1_1") (pintype "passive"))
      (node (ref "C16") (pin "1") (pinfunction "1_1") (pintype "passive"))
      (node (ref "C17") (pin "1") (pinfunction "1_1") (pintype "passive"))
      (node (ref "C2") (pin "1") (pinfunction "1_1") (pintype "passive"))
      (node (ref "C3") (pin "1") (pinfunction "1_1") (pintype "passive"))
      (node (ref "C4") (pin "1") (pinfunction "1_1") (pintype "passive"))
      (node (ref "C5") (pin "1") (pinfunction "1_1") (pintype "passive"))
      (node (ref "C6") (pin "1") (pinfunction "1_1") (pintype "passive"))
      (node (ref "C7") (pin "1") (pinfunction "1_1") (pintype "passive"))
      (node (ref "C8") (pin "1") (pinfunction "1_1") (pintype "passive"))
      (node (ref "C9") (pin "1") (pinfunction "1_1") (pintype "passive"))
      (node (ref "HL1") (pin "3") (pinfunction "A_3") (pintype "passive"))
      (node (ref "HL2") (pin "3") (pinfunction "A_3") (pintype "passive"))
      (node (ref "HL3") (pin "3") (pinfunction "A_3") (pintype "passive"))
      (node (ref "HL4") (pin "3") (pinfunction "A_3") (pintype "passive"))
      (node (ref "HL5") (pin "3") (pinfunction "A_3") (pintype "passive"))
      (node (ref "SB1") (pin "3") (pinfunction "3_3") (pintype "passive"))
      (node (ref "SB1") (pin "4") (pinfunction "4_4") (pintype "passive"))
      (node (ref "SB10") (pin "3") (pinfunction "3_3") (pintype "passive"))
      (node (ref "SB10") (pin "4") (pinfunction "4_4") (pintype "passive"))
      (node (ref "SB11") (pin "3") (pinfunction "3_3") (pintype "passive"))
      (node (ref "SB11") (pin "4") (pinfunction "4_4") (pintype "passive"))
      (node (ref "SB12") (pin "3") (pinfunction "3_3") (pintype "passive"))
      (node (ref "SB12") (pin "4") (pinfunction "4_4") (pintype "passive"))
      (node (ref "SB13") (pin "3") (pinfunction "3_3") (pintype "passive"))
      (node (ref "SB13") (pin "4") (pinfunction "4_4") (pintype "passive"))
      (node (ref "SB14") (pin "3") (pinfunction "3_3") (pintype "passive"))
      (node (ref "SB14") (pin "4") (pinfunction "4_4") (pintype "passive"))
      (node (ref "SB15") (pin "3") (pinfunction "3_3") (pintype "passive"))
      (node (ref "SB15") (pin "4") (pinfunction "4_4") (pintype "passive"))
      (node (ref "SB16") (pin "3") (pinfunction "3_3") (pintype "passive"))
      (node (ref "SB16") (pin "4") (pinfunction "4_4") (pintype "passive"))
      (node (ref "SB17") (pin "3") (pinfunction "3_3") (pintype "passive"))
      (node (ref "SB17") (pin "4") (pinfunction "4_4") (pintype "passive"))
      (node (ref "SB2") (pin "3") (pinfunction "3_3") (pintype "passive"))
      (node (ref "SB2") (pin "4") (pinfunction "4_4") (pintype "passive"))
      (node (ref "SB3") (pin "3") (pinfunction "3_3") (pintype "passive"))
      (node (ref "SB3") (pin "4") (pinfunction "4_4") (pintype "passive"))
      (node (ref "SB4") (pin "3") (pinfunction "3_3") (pintype "passive"))
      (node (ref "SB4") (pin "4") (pinfunction "4_4") (pintype "passive"))
      (node (ref "SB5") (pin "3") (pinfunction "3_3") (pintype "passive"))
      (node (ref "SB5") (pin "4") (pinfunction "4_4") (pintype "passive"))
      (node (ref "SB6") (pin "3") (pinfunction "3_3") (pintype "passive"))
      (node (ref "SB6") (pin "4") (pinfunction "4_4") (pintype "passive"))
      (node (ref "SB7") (pin "3") (pinfunction "3_3") (pintype "passive"))
      (node (ref "SB7") (pin "4") (pinfunction "4_4") (pintype "passive"))
      (node (ref "SB8") (pin "3") (pinfunction "3_3") (pintype "passive"))
      (node (ref "SB8") (pin "4") (pinfunction "4_4") (pintype "passive"))
      (node (ref "SB9") (pin "3") (pinfunction "3_3") (pintype "passive"))
      (node (ref "SB9") (pin "4") (pinfunction "4_4") (pintype "passive"))
      (node (ref "XP1") (pin "1") (pinfunction "1_1") (pintype "passive"))
    )
    (net (code "35") (name "Net-(HL1-B)") (class "Default")
      (node (ref "HL1") (pin "2") (pinfunction "B_2") (pintype "passive"))
      (node (ref "R1") (pin "1") (pinfunction "1_1") (pintype "passive"))
    )
    (net (code "36") (name "Net-(HL1-G)") (class "Default")
      (node (ref "HL1") (pin "1") (pinfunction "G_1") (pintype "passive"))
      (node (ref "R6") (pin "1") (pinfunction "1_1") (pintype "passive"))
    )
    (net (code "37") (name "Net-(HL1-R)") (class "Default")
      (node (ref "HL1") (pin "4") (pinfunction "R_4") (pintype "passive"))
      (node (ref "R7") (pin "1") (pinfunction "1_1") (pintype "passive"))
    )
    (net (code "38") (name "Net-(HL2-B)") (class "Default")
      (node (ref "HL2") (pin "2") (pinfunction "B_2") (pintype "passive"))
      (node (ref "R2") (pin "1") (pinfunction "1_1") (pintype "passive"))
    )
    (net (code "39") (name "Net-(HL2-G)") (class "Default")
      (node (ref "HL2") (pin "1") (pinfunction "G_1") (pintype "passive"))
      (node (ref "R8") (pin "1") (pinfunction "1_1") (pintype "passive"))
    )
    (net (code "40") (name "Net-(HL2-R)") (class "Default")
      (node (ref "HL2") (pin "4") (pinfunction "R_4") (pintype "passive"))
      (node (ref "R9") (pin "1") (pinfunction "1_1") (pintype "passive"))
    )
    (net (code "41") (name "Net-(HL3-B)") (class "Default")
      (node (ref "HL3") (pin "2") (pinfunction "B_2") (pintype "passive"))
      (node (ref "R3") (pin "1") (pinfunction "1_1") (pintype "passive"))
    )
    (net (code "42") (name "Net-(HL3-G)") (class "Default")
      (node (ref "HL3") (pin "1") (pinfunction "G_1") (pintype "passive"))
      (node (ref "R10") (pin "1") (pinfunction "1_1") (pintype "passive"))
    )
    (net (code "43") (name "Net-(HL3-R)") (class "Default")
      (node (ref "HL3") (pin "4") (pinfunction "R_4") (pintype "passive"))
      (node (ref "R11") (pin "1") (pinfunction "1_1") (pintype "passive"))
    )
    (net (code "44") (name "Net-(HL4-B)") (class "Default")
      (node (ref "HL4") (pin "2") (pinfunction "B_2") (pintype "passive"))
      (node (ref "R4") (pin "1") (pinfunction "1_1") (pintype "passive"))
    )
    (net (code "45") (name "Net-(HL4-G)") (class "Default")
      (node (ref "HL4") (pin "1") (pinfunction "G_1") (pintype "passive"))
      (node (ref "R12") (pin "1") (pinfunction "1_1") (pintype "passive"))
    )
    (net (code "46") (name "Net-(HL4-R)") (class "Default")
      (node (ref "HL4") (pin "4") (pinfunction "R_4") (pintype "passive"))
      (node (ref "R13") (pin "1") (pinfunction "1_1") (pintype "passive"))
    )
    (net (code "47") (name "Net-(HL5-B)") (class "Default")
      (node (ref "HL5") (pin "2") (pinfunction "B_2") (pintype "passive"))
      (node (ref "R5") (pin "1") (pinfunction "1_1") (pintype "passive"))
    )
    (net (code "48") (name "Net-(HL5-G)") (class "Default")
      (node (ref "HL5") (pin "1") (pinfunction "G_1") (pintype "passive"))
      (node (ref "R14") (pin "1") (pinfunction "1_1") (pintype "passive"))
    )
    (net (code "49") (name "Net-(HL5-R)") (class "Default")
      (node (ref "HL5") (pin "4") (pinfunction "R_4") (pintype "passive"))
      (node (ref "R15") (pin "1") (pinfunction "1_1") (pintype "passive"))
    )
  )
)
